# PowerSupply.net
KiCad netlist of a schematic drawn in Altium Designer
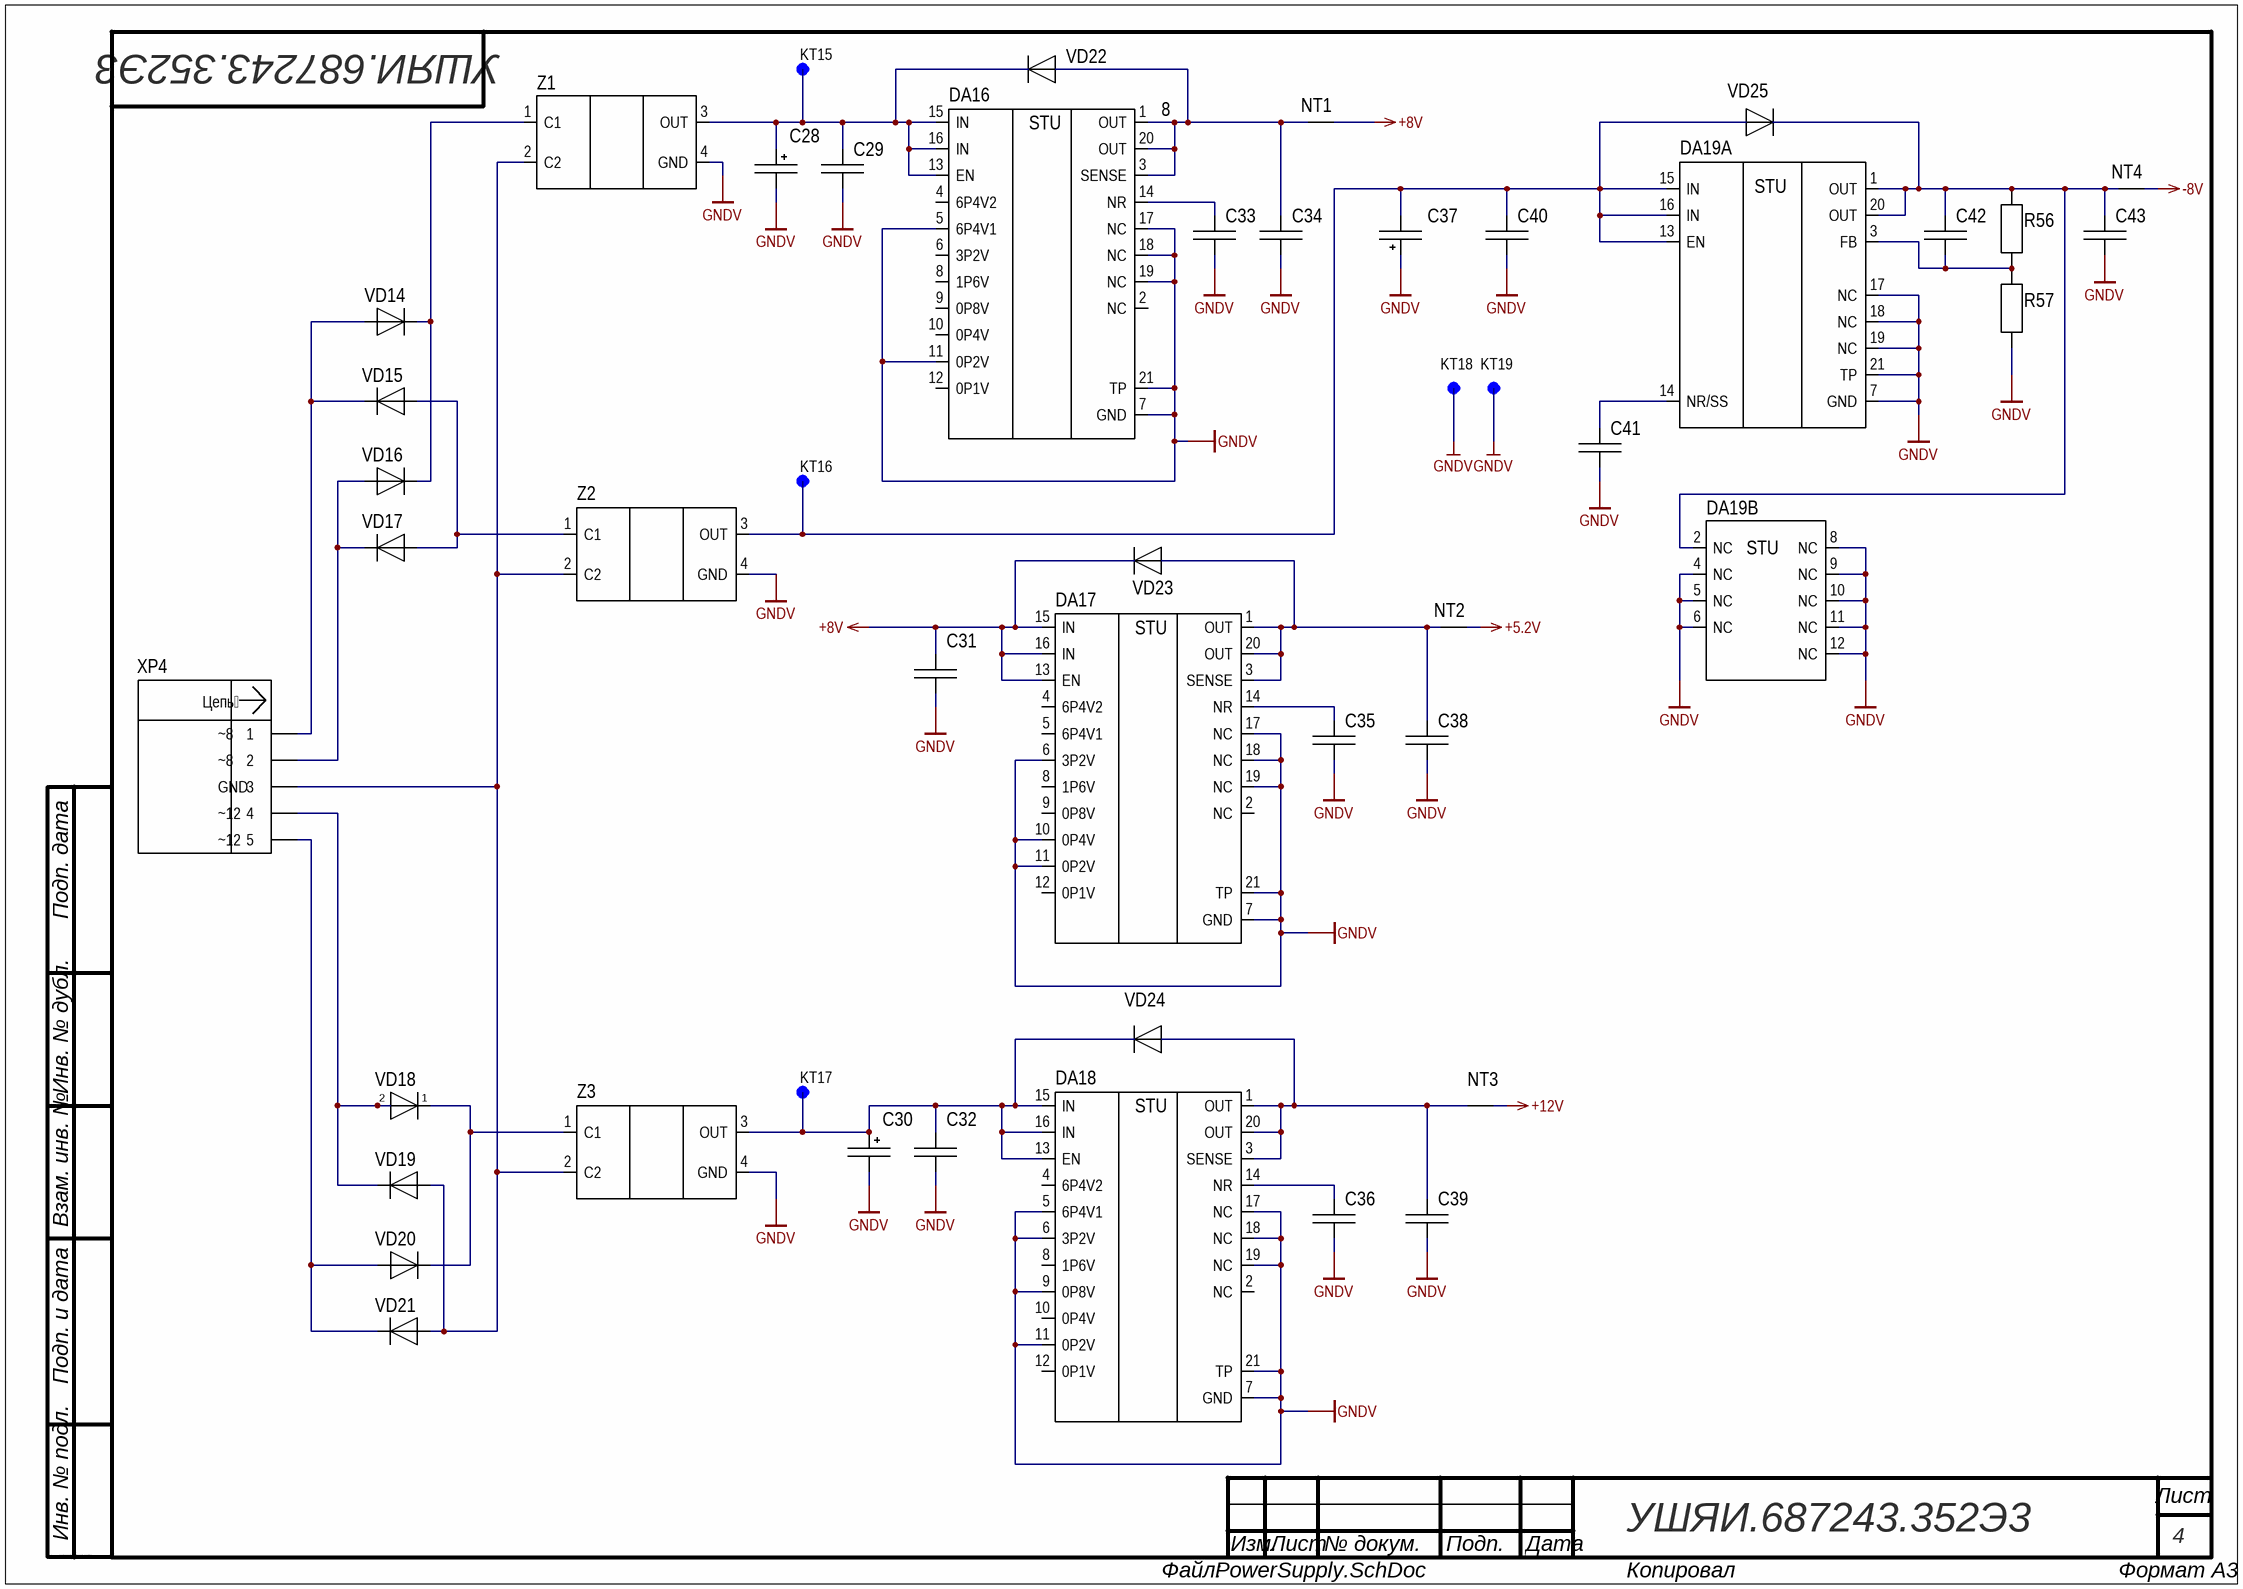
[diagram p0: PowerSupply.SchDoc]

(export (version "E")
  (design (tool "Eeschema 10.0.6"))
  (components
    (comp (ref "C28")
      (value "JRB-25В-1000 мкФ")
      (footprint "CAP TH ALUM ELEC D10.00mm S5.00mm H21.00mm")
      (libsource (lib "МНИПИ_Конденсаторы") (part "JRB-25В-1000 мкФ"))
    )
    (comp (ref "C29")
      (value "1206-X7R-50 B-10 мкФ+-10%")
      (footprint "standard-case:CAP: 1206")
      (libsource (lib "МНИПИ_Конденсаторы") (part "1206-X7R-50 B-10 мкФ+-10%"))
    )
    (comp (ref "C30")
      (value "JRB-35В-470мкФ")
      (footprint "CAP TH ALUM ELEC D10.00mm S5.00mm H17.00mm")
      (libsource (lib "МНИПИ_Конденсаторы") (part "JRB-35В-470мкФ"))
    )
    (comp (ref "C31")
      (value "1206-X7R-50 B-10 мкФ+-10%")
      (footprint "standard-case:CAP: 1206")
      (libsource (lib "МНИПИ_Конденсаторы") (part "1206-X7R-50 B-10 мкФ+-10%"))
    )
    (comp (ref "C32")
      (value "1206-X7R-50 B-10 мкФ+-10%")
      (footprint "standard-case:CAP: 1206")
      (libsource (lib "МНИПИ_Конденсаторы") (part "1206-X7R-50 B-10 мкФ+-10%"))
    )
    (comp (ref "C33")
      (value "0805-X7R-25 В-1 мкФ +-10%")
      (footprint "standard-case:CAP: 0805")
      (libsource (lib "МНИПИ_Конденсаторы") (part "0805-X7R-25 В-1 мкФ +-10%"))
    )
    (comp (ref "C34")
      (value "1206-X7R-25 B-47мкФ+-10%")
      (footprint "standard-case:CAP: 1206")
      (libsource (lib "МНИПИ_Конденсаторы") (part "1206-X7R-25 B-47мкФ+-10%"))
    )
    (comp (ref "C35")
      (value "0805-X7R-25 В-1 мкФ +-10%")
      (footprint "standard-case:CAP: 0805")
      (libsource (lib "МНИПИ_Конденсаторы") (part "0805-X7R-25 В-1 мкФ +-10%"))
    )
    (comp (ref "C36")
      (value "0805-X7R-25 В-1 мкФ +-10%")
      (footprint "standard-case:CAP: 0805")
      (libsource (lib "МНИПИ_Конденсаторы") (part "0805-X7R-25 В-1 мкФ +-10%"))
    )
    (comp (ref "C37")
      (value "JRB-25В-220мкФ")
      (footprint "CAP TH ALPOLY D8.00mm S3.50mm H12.00mm")
      (libsource (lib "МНИПИ_Конденсаторы") (part "JRB-25В-220мкФ"))
    )
    (comp (ref "C38")
      (value "1206-X7R-25 B-47мкФ+-10%")
      (footprint "standard-case:CAP: 1206")
      (libsource (lib "МНИПИ_Конденсаторы") (part "1206-X7R-25 B-47мкФ+-10%"))
    )
    (comp (ref "C39")
      (value "1206-X7R-25 B-47мкФ+-10%")
      (footprint "standard-case:CAP: 1206")
      (libsource (lib "МНИПИ_Конденсаторы") (part "1206-X7R-25 B-47мкФ+-10%"))
    )
    (comp (ref "C40")
      (value "1206-X7R-50 B-10 мкФ+-10%")
      (footprint "standard-case:CAP: 1206")
      (libsource (lib "МНИПИ_Конденсаторы") (part "1206-X7R-50 B-10 мкФ+-10%"))
    )
    (comp (ref "C41")
      (value "0805-X7R-25 В-1 мкФ +-10%")
      (footprint "standard-case:CAP: 0805")
      (libsource (lib "МНИПИ_Конденсаторы") (part "0805-X7R-25 В-1 мкФ +-10%"))
    )
    (comp (ref "C42")
      (value "1206-X7R-50 B-0,01 мкФ+-10%")
      (footprint "standard-case:CAP: 1206")
      (libsource (lib "МНИПИ_Конденсаторы") (part "1206-X7R-50 B-0,01 мкФ+-10%"))
    )
    (comp (ref "C43")
      (value "1206-X7R-25 B-47мкФ+-10%")
      (footprint "standard-case:CAP: 1206")
      (libsource (lib "МНИПИ_Конденсаторы") (part "1206-X7R-25 B-47мкФ+-10%"))
    )
    (comp (ref "DA16")
      (value "TPS7A4701")
      (footprint "20-VQFN")
      (description "TPS7A470x 36-V, 1-A, 4-µVRMS, RF LDO Voltage Regulator")
      (libsource (lib "МНИПИ_Микросхемы") (part "TPS7A4701"))
    )
    (comp (ref "DA17")
      (value "TPS7A4701")
      (footprint "20-VQFN")
      (description "TPS7A470x 36-V, 1-A, 4-µVRMS, RF LDO Voltage Regulator")
      (libsource (lib "МНИПИ_Микросхемы") (part "TPS7A4701"))
    )
    (comp (ref "DA18")
      (value "TPS7A4701")
      (footprint "20-VQFN")
      (description "TPS7A470x 36-V, 1-A, 4-µVRMS, RF LDO Voltage Regulator")
      (libsource (lib "МНИПИ_Микросхемы") (part "TPS7A4701"))
    )
    (comp (ref "DA19")
      (value "TPS7A3301")
      (footprint "20-VQFN")
      (description "TPS7A33 –36-V, 1-A, Ultralow-Noise Negative Voltage Regulator")
      (libsource (lib "МНИПИ_Микросхемы") (part "TPS7A3301"))
    )
    (comp (ref "KT15") (value "OTV10") (footprint "OTV10") (libsource (lib "МНИПИ_Остальное") (part "OTV10")))
    (comp (ref "KT16") (value "OTV10") (footprint "OTV10") (libsource (lib "МНИПИ_Остальное") (part "OTV10")))
    (comp (ref "KT17") (value "OTV10") (footprint "OTV10") (libsource (lib "МНИПИ_Остальное") (part "OTV10")))
    (comp (ref "KT18") (value "OTV10") (footprint "OTV10") (libsource (lib "МНИПИ_Остальное") (part "OTV10")))
    (comp (ref "KT19") (value "OTV10") (footprint "OTV10") (libsource (lib "МНИПИ_Остальное") (part "OTV10")))
    (comp (ref "NT1")
      (value "NetTie")
      (footprint "NetTie")
      (libsource (lib "МНИПИ_Остальное") (part "NetTie"))
    )
    (comp (ref "NT2")
      (value "NetTie")
      (footprint "NetTie")
      (libsource (lib "МНИПИ_Остальное") (part "NetTie"))
    )
    (comp (ref "NT3")
      (value "NetTie")
      (footprint "NetTie")
      (libsource (lib "МНИПИ_Остальное") (part "NetTie"))
    )
    (comp (ref "NT4")
      (value "NetTie")
      (footprint "NetTie")
      (libsource (lib "МНИПИ_Остальное") (part "NetTie"))
    )
    (comp (ref "R56")
      (value "1206-1,24 МОм+-1%")
      (footprint "МНИПИ_Резисторы:1206")
      (libsource (lib "МНИПИ_Резисторы") (part "1206-1,24 МОм+-1%"))
    )
    (comp (ref "R57")
      (value "1206-221 кОм+-1%")
      (footprint "МНИПИ_Резисторы:1206")
      (libsource (lib "МНИПИ_Резисторы") (part "1206-221 кОм+-1%"))
    )
    (comp (ref "VD14")
      (value "V1P22")
      (footprint "DO-219AD")
      (description "Surface-Mount TMBS® (Trench MOS Barrier Schottky) Rectifier")
      (libsource (lib "") (part "V1P22_1"))
    )
    (comp (ref "VD15")
      (value "V1P22")
      (footprint "DO-219AD")
      (description "Surface-Mount TMBS® (Trench MOS Barrier Schottky) Rectifier")
      (libsource (lib "") (part "V1P22_1"))
    )
    (comp (ref "VD16")
      (value "V1P22")
      (footprint "DO-219AD")
      (description "Surface-Mount TMBS® (Trench MOS Barrier Schottky) Rectifier")
      (libsource (lib "") (part "V1P22_1"))
    )
    (comp (ref "VD17")
      (value "V1P22")
      (footprint "DO-219AD")
      (description "Surface-Mount TMBS® (Trench MOS Barrier Schottky) Rectifier")
      (libsource (lib "") (part "V1P22_1"))
    )
    (comp (ref "VD18")
      (value "V1P22")
      (footprint "DO-219AD")
      (description "Surface-Mount TMBS® (Trench MOS Barrier Schottky) Rectifier")
      (libsource (lib "МНИПИ_Диоды") (part "V1P22"))
    )
    (comp (ref "VD19")
      (value "V1P22")
      (footprint "DO-219AD")
      (description "Surface-Mount TMBS® (Trench MOS Barrier Schottky) Rectifier")
      (libsource (lib "") (part "V1P22_1"))
    )
    (comp (ref "VD20")
      (value "V1P22")
      (footprint "DO-219AD")
      (description "Surface-Mount TMBS® (Trench MOS Barrier Schottky) Rectifier")
      (libsource (lib "") (part "V1P22_1"))
    )
    (comp (ref "VD21")
      (value "V1P22")
      (footprint "DO-219AD")
      (description "Surface-Mount TMBS® (Trench MOS Barrier Schottky) Rectifier")
      (libsource (lib "") (part "V1P22_1"))
    )
    (comp (ref "VD22")
      (value "1N4148WS")
      (footprint "SOD-323F")
      (description "Small Signal Fast Switching Diod")
      (libsource (lib "МНИПИ_Диоды") (part "1N4148WS"))
    )
    (comp (ref "VD23")
      (value "1N4148WS")
      (footprint "SOD-323F")
      (description "Small Signal Fast Switching Diod")
      (libsource (lib "МНИПИ_Диоды") (part "1N4148WS"))
    )
    (comp (ref "VD24")
      (value "1N4148WS")
      (footprint "SOD-323F")
      (description "Small Signal Fast Switching Diod")
      (libsource (lib "МНИПИ_Диоды") (part "1N4148WS"))
    )
    (comp (ref "VD25")
      (value "1N4148WS")
      (footprint "SOD-323F")
      (description "Small Signal Fast Switching Diod")
      (libsource (lib "МНИПИ_Диоды") (part "1N4148WS"))
    )
    (comp (ref "XP4")
      (value "DS1074-5MVT6")
      (footprint "DS1074-5MV")
      (libsource (lib "МНИПИ_Разъемы") (part "DS1074-5MVT6"))
    )
    (comp (ref "Z1")
      (value "BNX022-01")
      (footprint "BNX02")
      (libsource (lib "МНИПИ_Остальное") (part "BNX022-01"))
    )
    (comp (ref "Z2")
      (value "BNX022-01")
      (footprint "BNX02")
      (libsource (lib "МНИПИ_Остальное") (part "BNX022-01"))
    )
    (comp (ref "Z3")
      (value "BNX022-01")
      (footprint "BNX02")
      (libsource (lib "МНИПИ_Остальное") (part "BNX022-01"))
    )
  )
  (nets
    (net (code "1") (name "+5.2V") (class "Default")
      (node (ref "NT2") (pin "2") (pinfunction "N2_2") (pintype "passive"))
    )
    (net (code "2") (name "+8V") (class "Default")
      (node (ref "C31") (pin "2") (pinfunction "2_2") (pintype "passive"))
      (node (ref "DA17") (pin "13") (pinfunction "EN_13") (pintype "passive"))
      (node (ref "DA17") (pin "15") (pinfunction "IN_15") (pintype "passive"))
      (node (ref "DA17") (pin "16") (pinfunction "IN_16") (pintype "passive"))
      (node (ref "NT1") (pin "2") (pinfunction "N2_2") (pintype "passive"))
      (node (ref "VD23") (pin "1") (pintype "passive"))
    )
    (net (code "3") (name "+12V") (class "Default")
      (node (ref "NT3") (pin "2") (pinfunction "N2_2") (pintype "passive"))
    )
    (net (code "4") (name "-8V") (class "Default")
      (node (ref "NT4") (pin "2") (pinfunction "N2_2") (pintype "passive"))
    )
    (net (code "5") (name "GNDV") (class "Default")
      (node (ref "C28") (pin "2") (pinfunction "2_2") (pintype "passive"))
      (node (ref "C29") (pin "1") (pinfunction "1_1") (pintype "passive"))
      (node (ref "C30") (pin "2") (pinfunction "2_2") (pintype "passive"))
      (node (ref "C31") (pin "1") (pinfunction "1_1") (pintype "passive"))
      (node (ref "C32") (pin "1") (pinfunction "1_1") (pintype "passive"))
      (node (ref "C33") (pin "1") (pinfunction "1_1") (pintype "passive"))
      (node (ref "C34") (pin "1") (pinfunction "1_1") (pintype "passive"))
      (node (ref "C35") (pin "1") (pinfunction "1_1") (pintype "passive"))
      (node (ref "C36") (pin "1") (pinfunction "1_1") (pintype "passive"))
      (node (ref "C37") (pin "1") (pinfunction "1_1") (pintype "passive"))
      (node (ref "C38") (pin "1") (pinfunction "1_1") (pintype "passive"))
      (node (ref "C39") (pin "1") (pinfunction "1_1") (pintype "passive"))
      (node (ref "C40") (pin "1") (pinfunction "1_1") (pintype "passive"))
      (node (ref "C41") (pin "1") (pinfunction "1_1") (pintype "passive"))
      (node (ref "C43") (pin "1") (pinfunction "1_1") (pintype "passive"))
      (node (ref "DA16") (pin "11") (pinfunction "0P2V_11") (pintype "passive"))
      (node (ref "DA16") (pin "17") (pinfunction "NC_17") (pintype "passive"))
      (node (ref "DA16") (pin "18") (pinfunction "NC_18") (pintype "passive"))
      (node (ref "DA16") (pin "19") (pinfunction "NC_19") (pintype "passive"))
      (node (ref "DA16") (pin "21") (pinfunction "TP_21") (pintype "passive"))
      (node (ref "DA16") (pin "5") (pinfunction "6P4V1_5") (pintype "passive"))
      (node (ref "DA16") (pin "7") (pinfunction "GND_7") (pintype "passive"))
      (node (ref "DA17") (pin "10") (pinfunction "0P4V_10") (pintype "passive"))
      (node (ref "DA17") (pin "11") (pinfunction "0P2V_11") (pintype "passive"))
      (node (ref "DA17") (pin "17") (pinfunction "NC_17") (pintype "passive"))
      (node (ref "DA17") (pin "18") (pinfunction "NC_18") (pintype "passive"))
      (node (ref "DA17") (pin "19") (pinfunction "NC_19") (pintype "passive"))
      (node (ref "DA17") (pin "21") (pinfunction "TP_21") (pintype "passive"))
      (node (ref "DA17") (pin "6") (pinfunction "3P2V_6") (pintype "passive"))
      (node (ref "DA17") (pin "7") (pinfunction "GND_7") (pintype "passive"))
      (node (ref "DA18") (pin "11") (pinfunction "0P2V_11") (pintype "passive"))
      (node (ref "DA18") (pin "17") (pinfunction "NC_17") (pintype "passive"))
      (node (ref "DA18") (pin "18") (pinfunction "NC_18") (pintype "passive"))
      (node (ref "DA18") (pin "19") (pinfunction "NC_19") (pintype "passive"))
      (node (ref "DA18") (pin "21") (pinfunction "TP_21") (pintype "passive"))
      (node (ref "DA18") (pin "5") (pinfunction "6P4V1_5") (pintype "passive"))
      (node (ref "DA18") (pin "6") (pinfunction "3P2V_6") (pintype "passive"))
      (node (ref "DA18") (pin "7") (pinfunction "GND_7") (pintype "passive"))
      (node (ref "DA18") (pin "9") (pinfunction "0P8V_9") (pintype "passive"))
      (node (ref "DA19") (pin "10") (pinfunction "NC_10") (pintype "passive"))
      (node (ref "DA19") (pin "11") (pinfunction "NC_11") (pintype "passive"))
      (node (ref "DA19") (pin "12") (pinfunction "NC_12") (pintype "passive"))
      (node (ref "DA19") (pin "17") (pinfunction "NC_17") (pintype "passive"))
      (node (ref "DA19") (pin "18") (pinfunction "NC_18") (pintype "passive"))
      (node (ref "DA19") (pin "19") (pinfunction "NC_19") (pintype "passive"))
      (node (ref "DA19") (pin "21") (pinfunction "TP_21") (pintype "passive"))
      (node (ref "DA19") (pin "4") (pinfunction "NC_4") (pintype "passive"))
      (node (ref "DA19") (pin "5") (pinfunction "NC_5") (pintype "passive"))
      (node (ref "DA19") (pin "6") (pinfunction "NC_6") (pintype "passive"))
      (node (ref "DA19") (pin "7") (pinfunction "GND_7") (pintype "passive"))
      (node (ref "DA19") (pin "8") (pinfunction "NC_8") (pintype "passive"))
      (node (ref "DA19") (pin "9") (pinfunction "NC_9") (pintype "passive"))
      (node (ref "KT18") (pin "1") (pinfunction "1_1") (pintype "passive"))
      (node (ref "KT19") (pin "1") (pinfunction "1_1") (pintype "passive"))
      (node (ref "R57") (pin "1") (pinfunction "1_1") (pintype "passive"))
      (node (ref "Z1") (pin "4") (pinfunction "GND_4") (pintype "passive"))
      (node (ref "Z2") (pin "4") (pinfunction "GND_4") (pintype "passive"))
      (node (ref "Z3") (pin "4") (pinfunction "GND_4") (pintype "passive"))
    )
    (net (code "6") (name "Net-(DA16-EN)") (class "Default")
      (node (ref "C28") (pin "1") (pinfunction "1_1") (pintype "passive"))
      (node (ref "C29") (pin "2") (pinfunction "2_2") (pintype "passive"))
      (node (ref "DA16") (pin "13") (pinfunction "EN_13") (pintype "passive"))
      (node (ref "DA16") (pin "15") (pinfunction "IN_15") (pintype "passive"))
      (node (ref "DA16") (pin "16") (pinfunction "IN_16") (pintype "passive"))
      (node (ref "KT15") (pin "1") (pinfunction "1_1") (pintype "passive"))
      (node (ref "VD22") (pin "1") (pintype "passive"))
      (node (ref "Z1") (pin "3") (pinfunction "OUT_3") (pintype "passive"))
    )
    (net (code "7") (name "Net-(DA16-NR)") (class "Default")
      (node (ref "C33") (pin "2") (pinfunction "2_2") (pintype "passive"))
      (node (ref "DA16") (pin "14") (pinfunction "NR_14") (pintype "passive"))
    )
    (net (code "8") (name "Net-(DA16-SENSE)") (class "Default")
      (node (ref "C34") (pin "2") (pinfunction "2_2") (pintype "passive"))
      (node (ref "DA16") (pin "1") (pinfunction "OUT_1") (pintype "passive"))
      (node (ref "DA16") (pin "20") (pinfunction "OUT_20") (pintype "passive"))
      (node (ref "DA16") (pin "3") (pinfunction "SENSE_3") (pintype "passive"))
      (node (ref "NT1") (pin "1") (pinfunction "N1_1") (pintype "passive"))
      (node (ref "VD22") (pin "2") (pintype "passive"))
    )
    (net (code "9") (name "Net-(DA17-NR)") (class "Default")
      (node (ref "C35") (pin "2") (pinfunction "2_2") (pintype "passive"))
      (node (ref "DA17") (pin "14") (pinfunction "NR_14") (pintype "passive"))
    )
    (net (code "10") (name "Net-(DA17-SENSE)") (class "Default")
      (node (ref "C38") (pin "2") (pinfunction "2_2") (pintype "passive"))
      (node (ref "DA17") (pin "1") (pinfunction "OUT_1") (pintype "passive"))
      (node (ref "DA17") (pin "20") (pinfunction "OUT_20") (pintype "passive"))
      (node (ref "DA17") (pin "3") (pinfunction "SENSE_3") (pintype "passive"))
      (node (ref "NT2") (pin "1") (pinfunction "N1_1") (pintype "passive"))
      (node (ref "VD23") (pin "2") (pintype "passive"))
    )
    (net (code "11") (name "Net-(DA18-EN)") (class "Default")
      (node (ref "C30") (pin "1") (pinfunction "1_1") (pintype "passive"))
      (node (ref "C32") (pin "2") (pinfunction "2_2") (pintype "passive"))
      (node (ref "DA18") (pin "13") (pinfunction "EN_13") (pintype "passive"))
      (node (ref "DA18") (pin "15") (pinfunction "IN_15") (pintype "passive"))
      (node (ref "DA18") (pin "16") (pinfunction "IN_16") (pintype "passive"))
      (node (ref "KT17") (pin "1") (pinfunction "1_1") (pintype "passive"))
      (node (ref "VD24") (pin "1") (pintype "passive"))
      (node (ref "Z3") (pin "3") (pinfunction "OUT_3") (pintype "passive"))
    )
    (net (code "12") (name "Net-(DA18-NR)") (class "Default")
      (node (ref "C36") (pin "2") (pinfunction "2_2") (pintype "passive"))
      (node (ref "DA18") (pin "14") (pinfunction "NR_14") (pintype "passive"))
    )
    (net (code "13") (name "Net-(DA18-SENSE)") (class "Default")
      (node (ref "C39") (pin "2") (pinfunction "2_2") (pintype "passive"))
      (node (ref "DA18") (pin "1") (pinfunction "OUT_1") (pintype "passive"))
      (node (ref "DA18") (pin "20") (pinfunction "OUT_20") (pintype "passive"))
      (node (ref "DA18") (pin "3") (pinfunction "SENSE_3") (pintype "passive"))
      (node (ref "NT3") (pin "1") (pinfunction "N1_1") (pintype "passive"))
      (node (ref "VD24") (pin "2") (pintype "passive"))
    )
    (net (code "14") (name "Net-(DA19A-EN)") (class "Default")
      (node (ref "C37") (pin "2") (pinfunction "2_2") (pintype "passive"))
      (node (ref "C40") (pin "2") (pinfunction "2_2") (pintype "passive"))
      (node (ref "DA19") (pin "13") (pinfunction "EN_13") (pintype "passive"))
      (node (ref "DA19") (pin "15") (pinfunction "IN_15") (pintype "passive"))
      (node (ref "DA19") (pin "16") (pinfunction "IN_16") (pintype "passive"))
      (node (ref "KT16") (pin "1") (pinfunction "1_1") (pintype "passive"))
      (node (ref "VD25") (pin "2") (pintype "passive"))
      (node (ref "Z2") (pin "3") (pinfunction "OUT_3") (pintype "passive"))
    )
    (net (code "15") (name "Net-(DA19A-FB)") (class "Default")
      (node (ref "C42") (pin "1") (pinfunction "1_1") (pintype "passive"))
      (node (ref "DA19") (pin "3") (pinfunction "FB_3") (pintype "passive"))
      (node (ref "R56") (pin "1") (pinfunction "1_1") (pintype "passive"))
      (node (ref "R57") (pin "2") (pinfunction "2_2") (pintype "passive"))
    )
    (net (code "16") (name "Net-(DA19A-NR{slash}SS)") (class "Default")
      (node (ref "C41") (pin "2") (pinfunction "2_2") (pintype "passive"))
      (node (ref "DA19") (pin "14") (pinfunction "NR/SS_14") (pintype "passive"))
    )
    (net (code "17") (name "Net-(NT4-N1)") (class "Default")
      (node (ref "C42") (pin "2") (pinfunction "2_2") (pintype "passive"))
      (node (ref "C43") (pin "2") (pinfunction "2_2") (pintype "passive"))
      (node (ref "DA19") (pin "1") (pinfunction "OUT_1") (pintype "passive"))
      (node (ref "DA19") (pin "2") (pinfunction "NC_2") (pintype "passive"))
      (node (ref "DA19") (pin "20") (pinfunction "OUT_20") (pintype "passive"))
      (node (ref "NT4") (pin "1") (pinfunction "N1_1") (pintype "passive"))
      (node (ref "R56") (pin "2") (pinfunction "2_2") (pintype "passive"))
      (node (ref "VD25") (pin "1") (pintype "passive"))
    )
    (net (code "18") (name "Net-(VD14-Anode)") (class "Default")
      (node (ref "VD14") (pin "2") (pinfunction "Anode_2") (pintype "passive"))
      (node (ref "VD15") (pin "1") (pinfunction "Cathode_1") (pintype "passive"))
      (node (ref "XP4") (pin "1") (pinfunction "1_1") (pintype "passive"))
    )
    (net (code "19") (name "Net-(VD14-Cathode)") (class "Default")
      (node (ref "VD14") (pin "1") (pinfunction "Cathode_1") (pintype "passive"))
      (node (ref "VD16") (pin "1") (pinfunction "Cathode_1") (pintype "passive"))
      (node (ref "Z1") (pin "1") (pinfunction "С1_1") (pintype "passive"))
    )
    (net (code "20") (name "Net-(VD15-Anode)") (class "Default")
      (node (ref "VD15") (pin "2") (pinfunction "Anode_2") (pintype "passive"))
      (node (ref "VD17") (pin "2") (pinfunction "Anode_2") (pintype "passive"))
      (node (ref "Z2") (pin "1") (pinfunction "С1_1") (pintype "passive"))
    )
    (net (code "21") (name "Net-(VD16-Anode)") (class "Default")
      (node (ref "VD16") (pin "2") (pinfunction "Anode_2") (pintype "passive"))
      (node (ref "VD17") (pin "1") (pinfunction "Cathode_1") (pintype "passive"))
      (node (ref "XP4") (pin "2") (pinfunction "2_2") (pintype "passive"))
    )
    (net (code "22") (name "Net-(VD18-Anode)") (class "Default")
      (node (ref "VD18") (pin "2") (pinfunction "Anode_2") (pintype "passive"))
      (node (ref "VD19") (pin "1") (pinfunction "Cathode_1") (pintype "passive"))
      (node (ref "XP4") (pin "4") (pinfunction "4_4") (pintype "passive"))
    )
    (net (code "23") (name "Net-(VD18-Cathode)") (class "Default")
      (node (ref "VD18") (pin "1") (pinfunction "Cathode_1") (pintype "passive"))
      (node (ref "VD20") (pin "1") (pinfunction "Cathode_1") (pintype "passive"))
      (node (ref "Z3") (pin "1") (pinfunction "С1_1") (pintype "passive"))
    )
    (net (code "24") (name "Net-(VD19-Anode)") (class "Default")
      (node (ref "VD19") (pin "2") (pinfunction "Anode_2") (pintype "passive"))
      (node (ref "VD21") (pin "2") (pinfunction "Anode_2") (pintype "passive"))
      (node (ref "XP4") (pin "3") (pinfunction "3_3") (pintype "passive"))
      (node (ref "Z1") (pin "2") (pinfunction "C2_2") (pintype "passive"))
      (node (ref "Z2") (pin "2") (pinfunction "C2_2") (pintype "passive"))
      (node (ref "Z3") (pin "2") (pinfunction "C2_2") (pintype "passive"))
    )
    (net (code "25") (name "Net-(VD20-Anode)") (class "Default")
      (node (ref "VD20") (pin "2") (pinfunction "Anode_2") (pintype "passive"))
      (node (ref "VD21") (pin "1") (pinfunction "Cathode_1") (pintype "passive"))
      (node (ref "XP4") (pin "5") (pinfunction "5_5") (pintype "passive"))
    )
    (net (code "26") (name "unconnected-(DA16-0P1V-Pad12)") (class "Default")
      (node (ref "DA16") (pin "12") (pinfunction "0P1V_12") (pintype "passive"))
    )
    (net (code "27") (name "unconnected-(DA16-0P4V-Pad10)") (class "Default")
      (node (ref "DA16") (pin "10") (pinfunction "0P4V_10") (pintype "passive"))
    )
    (net (code "28") (name "unconnected-(DA16-0P8V-Pad9)") (class "Default")
      (node (ref "DA16") (pin "9") (pinfunction "0P8V_9") (pintype "passive"))
    )
    (net (code "29") (name "unconnected-(DA16-1P6V-Pad8)") (class "Default")
      (node (ref "DA16") (pin "8") (pinfunction "1P6V_8") (pintype "passive"))
    )
    (net (code "30") (name "unconnected-(DA16-3P2V-Pad6)") (class "Default")
      (node (ref "DA16") (pin "6") (pinfunction "3P2V_6") (pintype "passive"))
    )
    (net (code "31") (name "unconnected-(DA16-6P4V2-Pad4)") (class "Default")
      (node (ref "DA16") (pin "4") (pinfunction "6P4V2_4") (pintype "passive"))
    )
    (net (code "32") (name "unconnected-(DA16-NC-Pad2)") (class "Default")
      (node (ref "DA16") (pin "2") (pinfunction "NC_2") (pintype "passive"))
    )
    (net (code "33") (name "unconnected-(DA17-0P1V-Pad12)") (class "Default")
      (node (ref "DA17") (pin "12") (pinfunction "0P1V_12") (pintype "passive"))
    )
    (net (code "34") (name "unconnected-(DA17-0P8V-Pad9)") (class "Default")
      (node (ref "DA17") (pin "9") (pinfunction "0P8V_9") (pintype "passive"))
    )
    (net (code "35") (name "unconnected-(DA17-1P6V-Pad8)") (class "Default")
      (node (ref "DA17") (pin "8") (pinfunction "1P6V_8") (pintype "passive"))
    )
    (net (code "36") (name "unconnected-(DA17-6P4V1-Pad5)") (class "Default")
      (node (ref "DA17") (pin "5") (pinfunction "6P4V1_5") (pintype "passive"))
    )
    (net (code "37") (name "unconnected-(DA17-6P4V2-Pad4)") (class "Default")
      (node (ref "DA17") (pin "4") (pinfunction "6P4V2_4") (pintype "passive"))
    )
    (net (code "38") (name "unconnected-(DA17-NC-Pad2)") (class "Default")
      (node (ref "DA17") (pin "2") (pinfunction "NC_2") (pintype "passive"))
    )
    (net (code "39") (name "unconnected-(DA18-0P1V-Pad12)") (class "Default")
      (node (ref "DA18") (pin "12") (pinfunction "0P1V_12") (pintype "passive"))
    )
    (net (code "40") (name "unconnected-(DA18-0P4V-Pad10)") (class "Default")
      (node (ref "DA18") (pin "10") (pinfunction "0P4V_10") (pintype "passive"))
    )
    (net (code "41") (name "unconnected-(DA18-1P6V-Pad8)") (class "Default")
      (node (ref "DA18") (pin "8") (pinfunction "1P6V_8") (pintype "passive"))
    )
    (net (code "42") (name "unconnected-(DA18-6P4V2-Pad4)") (class "Default")
      (node (ref "DA18") (pin "4") (pinfunction "6P4V2_4") (pintype "passive"))
    )
    (net (code "43") (name "unconnected-(DA18-NC-Pad2)") (class "Default")
      (node (ref "DA18") (pin "2") (pinfunction "NC_2") (pintype "passive"))
    )
  )
)
